# usb_cdcacm.net
KiCad netlist of a schematic drawn in EAGLE
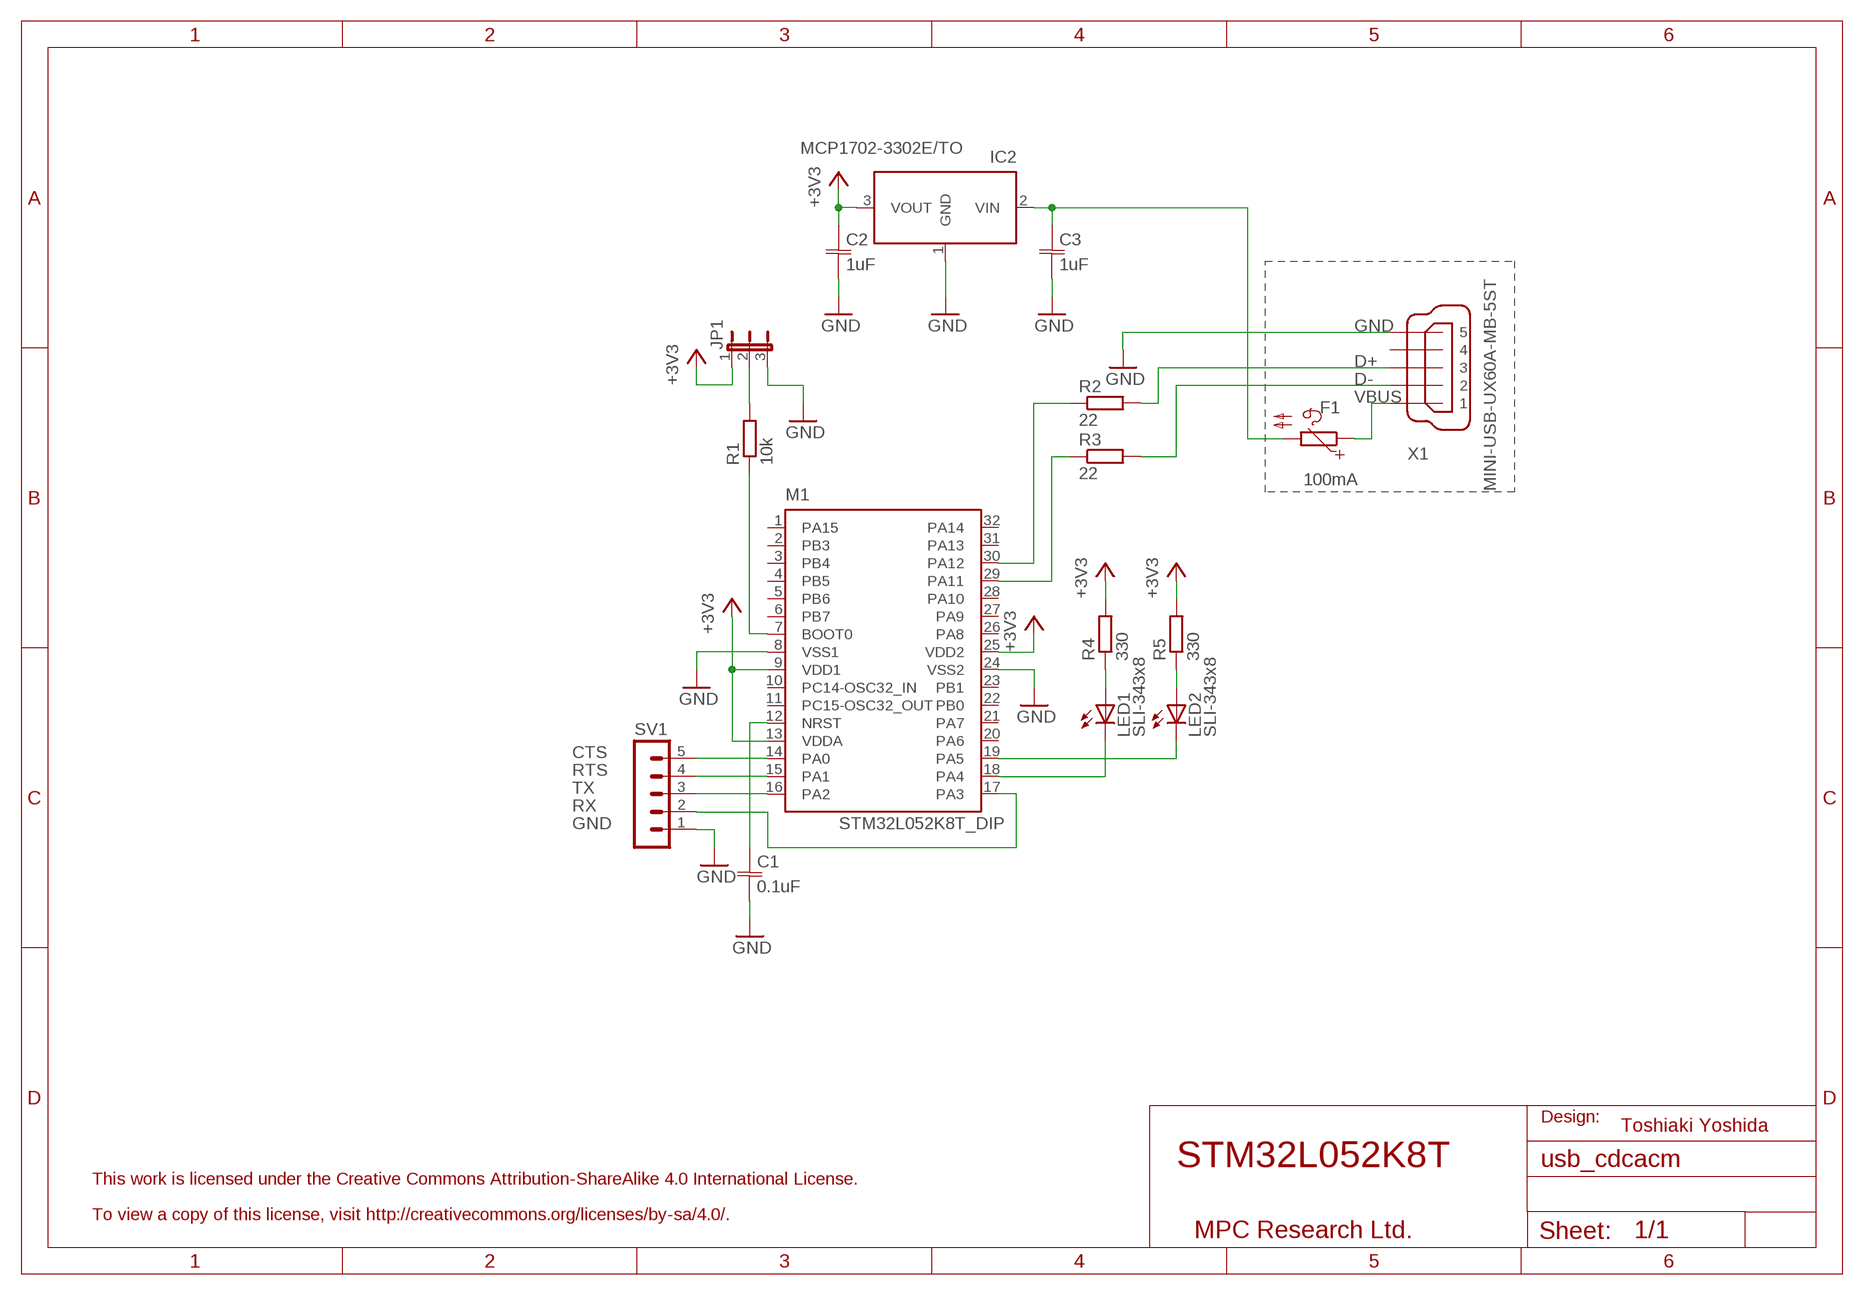
[diagram p0: schematic, sheet 1]

(export (version "E")
  (design (tool "Eeschema 10.0.6"))
  (components
    (comp (ref "C1")
      (value "0.1uF")
      (footprint "eagle-import:C050-024X044")
      (libsource (lib "eagle-import") (part "C-JIS050-024X044"))
    )
    (comp (ref "C2")
      (value "1uF")
      (footprint "eagle-import:C050-024X044")
      (libsource (lib "eagle-import") (part "C-JIS050-024X044"))
    )
    (comp (ref "C3")
      (value "1uF")
      (footprint "eagle-import:C050-024X044")
      (libsource (lib "eagle-import") (part "C-JIS050-024X044"))
    )
    (comp (ref "F1")
      (value "100mA")
      (footprint "eagle-import:1206")
      (libsource (lib "eagle-import") (part "PTC1206"))
    )
    (comp (ref "IC2")
      (value "MCP1702-3302E/TO")
      (footprint "eagle-import:TO92")
      (fields (field (name "VOLTAGE") "3.3V"))
      (libsource (lib "eagle-import") (part "MCP1702TO-3302E/"))
    )
    (comp (ref "JP1")
      (value "JP2E")
      (footprint "eagle-import:JP2")
      (libsource (lib "eagle-import") (part "JP2E"))
    )
    (comp (ref "LED1")
      (value "SLI-343x8")
      (footprint "eagle-import:LED3MM")
      (libsource (lib "eagle-import") (part "LED3MM"))
    )
    (comp (ref "LED2")
      (value "SLI-343x8")
      (footprint "eagle-import:LED3MM")
      (libsource (lib "eagle-import") (part "LED3MM"))
    )
    (comp (ref "M1")
      (value "STM32L052K8T_DIP")
      (footprint "eagle-import:DIP32")
      (libsource (lib "eagle-import") (part "STM32L052K8T_DIP"))
    )
    (comp (ref "R1")
      (value "10k")
      (footprint "eagle-import:0207_2V")
      (libsource (lib "eagle-import") (part "R-EU_0207/2V"))
    )
    (comp (ref "R2")
      (value "22")
      (footprint "eagle-import:0207_10")
      (libsource (lib "eagle-import") (part "R-EU_0207/10"))
    )
    (comp (ref "R3")
      (value "22")
      (footprint "eagle-import:0207_10")
      (libsource (lib "eagle-import") (part "R-EU_0207/10"))
    )
    (comp (ref "R4")
      (value "330")
      (footprint "eagle-import:0207_2V")
      (libsource (lib "eagle-import") (part "R-EU_0207/2V"))
    )
    (comp (ref "R5")
      (value "330")
      (footprint "eagle-import:0207_2V")
      (libsource (lib "eagle-import") (part "R-EU_0207/2V"))
    )
    (comp (ref "SV1")
      (value "MA05-1")
      (footprint "eagle-import:MA05-1")
      (libsource (lib "eagle-import") (part "MA05-1"))
    )
    (comp (ref "X1")
      (value "MINI-USB-UX60A-MB-5ST")
      (footprint "eagle-import:UX60A-MB-5ST")
      (libsource (lib "eagle-import") (part "MINI-USB-UX60A-MB-5ST"))
    )
  )
  (nets
    (net (code "1") (name "+3V3") (class "Default")
      (node (ref "C2") (pin "1") (pinfunction "1_1") (pintype "passive"))
      (node (ref "IC2") (pin "3") (pinfunction "VOUT_3") (pintype "power_in"))
      (node (ref "JP1") (pin "1") (pinfunction "1_1") (pintype "passive"))
      (node (ref "M1") (pin "13") (pinfunction "VDDA_13") (pintype "power_in"))
      (node (ref "M1") (pin "25") (pinfunction "VDD2_25") (pintype "bidirectional"))
      (node (ref "M1") (pin "9") (pinfunction "VDD1_9") (pintype "power_in"))
      (node (ref "R4") (pin "2") (pinfunction "2_2") (pintype "passive"))
      (node (ref "R5") (pin "2") (pinfunction "2_2") (pintype "passive"))
    )
    (net (code "2") (name "GND") (class "Default")
      (node (ref "C1") (pin "2") (pinfunction "2_2") (pintype "passive"))
      (node (ref "C2") (pin "2") (pinfunction "2_2") (pintype "passive"))
      (node (ref "C3") (pin "2") (pinfunction "2_2") (pintype "passive"))
      (node (ref "IC2") (pin "1") (pinfunction "GND_1") (pintype "power_in"))
      (node (ref "JP1") (pin "3") (pinfunction "3_3") (pintype "passive"))
      (node (ref "M1") (pin "24") (pinfunction "VSS2_24") (pintype "power_in"))
      (node (ref "M1") (pin "8") (pinfunction "VSS1_8") (pintype "power_in"))
      (node (ref "SV1") (pin "1") (pinfunction "1_1") (pintype "passive"))
      (node (ref "X1") (pin "5") (pinfunction "5_5") (pintype "input"))
    )
    (net (code "3") (name "Net-(F1-Pad1)") (class "Default")
      (node (ref "F1") (pin "1") (pinfunction "1_1") (pintype "passive"))
      (node (ref "X1") (pin "1") (pinfunction "1_1") (pintype "input"))
    )
    (net (code "4") (name "Net-(IC2-VIN)") (class "Default")
      (node (ref "C3") (pin "1") (pinfunction "1_1") (pintype "passive"))
      (node (ref "F1") (pin "2") (pinfunction "2_2") (pintype "passive"))
      (node (ref "IC2") (pin "2") (pinfunction "VIN_2") (pintype "power_in"))
    )
    (net (code "5") (name "Net-(JP1-Pad2)") (class "Default")
      (node (ref "JP1") (pin "2") (pinfunction "2_2") (pintype "passive"))
      (node (ref "R1") (pin "2") (pinfunction "2_2") (pintype "passive"))
    )
    (net (code "6") (name "Net-(LED1-C)") (class "Default")
      (node (ref "LED1") (pin "K") (pinfunction "C_K") (pintype "passive"))
      (node (ref "M1") (pin "18") (pinfunction "PA4_18") (pintype "bidirectional"))
    )
    (net (code "7") (name "Net-(LED1-PadA)") (class "Default")
      (node (ref "LED1") (pin "A") (pinfunction "A_A") (pintype "passive"))
      (node (ref "R4") (pin "1") (pinfunction "1_1") (pintype "passive"))
    )
    (net (code "8") (name "Net-(LED2-C)") (class "Default")
      (node (ref "LED2") (pin "K") (pinfunction "C_K") (pintype "passive"))
      (node (ref "M1") (pin "19") (pinfunction "PA5_19") (pintype "bidirectional"))
    )
    (net (code "9") (name "Net-(LED2-PadA)") (class "Default")
      (node (ref "LED2") (pin "A") (pinfunction "A_A") (pintype "passive"))
      (node (ref "R5") (pin "1") (pinfunction "1_1") (pintype "passive"))
    )
    (net (code "10") (name "Net-(M1-BOOT0)") (class "Default")
      (node (ref "M1") (pin "7") (pinfunction "BOOT0_7") (pintype "bidirectional"))
      (node (ref "R1") (pin "1") (pinfunction "1_1") (pintype "passive"))
    )
    (net (code "11") (name "Net-(M1-NRST)") (class "Default")
      (node (ref "C1") (pin "1") (pinfunction "1_1") (pintype "passive"))
      (node (ref "M1") (pin "12") (pinfunction "NRST_12") (pintype "bidirectional"))
    )
    (net (code "12") (name "Net-(M1-PA0)") (class "Default")
      (node (ref "M1") (pin "14") (pinfunction "PA0_14") (pintype "bidirectional"))
      (node (ref "SV1") (pin "5") (pinfunction "5_5") (pintype "passive"))
    )
    (net (code "13") (name "Net-(M1-PA1)") (class "Default")
      (node (ref "M1") (pin "15") (pinfunction "PA1_15") (pintype "bidirectional"))
      (node (ref "SV1") (pin "4") (pinfunction "4_4") (pintype "passive"))
    )
    (net (code "14") (name "Net-(M1-PA2)") (class "Default")
      (node (ref "M1") (pin "16") (pinfunction "PA2_16") (pintype "bidirectional"))
      (node (ref "SV1") (pin "3") (pinfunction "3_3") (pintype "passive"))
    )
    (net (code "15") (name "Net-(M1-PA3)") (class "Default")
      (node (ref "M1") (pin "17") (pinfunction "PA3_17") (pintype "bidirectional"))
      (node (ref "SV1") (pin "2") (pinfunction "2_2") (pintype "passive"))
    )
    (net (code "16") (name "Net-(M1-PA11)") (class "Default")
      (node (ref "M1") (pin "29") (pinfunction "PA11_29") (pintype "bidirectional"))
      (node (ref "R3") (pin "1") (pinfunction "1_1") (pintype "passive"))
    )
    (net (code "17") (name "Net-(M1-PA12)") (class "Default")
      (node (ref "M1") (pin "30") (pinfunction "PA12_30") (pintype "bidirectional"))
      (node (ref "R2") (pin "1") (pinfunction "1_1") (pintype "passive"))
    )
    (net (code "18") (name "Net-(R2-Pad2)") (class "Default")
      (node (ref "R2") (pin "2") (pinfunction "2_2") (pintype "passive"))
      (node (ref "X1") (pin "3") (pinfunction "3_3") (pintype "input"))
    )
    (net (code "19") (name "Net-(R3-Pad2)") (class "Default")
      (node (ref "R3") (pin "2") (pinfunction "2_2") (pintype "passive"))
      (node (ref "X1") (pin "2") (pinfunction "2_2") (pintype "input"))
    )
    (net (code "20") (name "unconnected-(M1-PA6-Pad20)") (class "Default")
      (node (ref "M1") (pin "20") (pinfunction "PA6_20") (pintype "bidirectional"))
    )
    (net (code "21") (name "unconnected-(M1-PA7-Pad21)") (class "Default")
      (node (ref "M1") (pin "21") (pinfunction "PA7_21") (pintype "bidirectional"))
    )
    (net (code "22") (name "unconnected-(M1-PA8-Pad26)") (class "Default")
      (node (ref "M1") (pin "26") (pinfunction "PA8_26") (pintype "bidirectional"))
    )
    (net (code "23") (name "unconnected-(M1-PA9-Pad27)") (class "Default")
      (node (ref "M1") (pin "27") (pinfunction "PA9_27") (pintype "bidirectional"))
    )
    (net (code "24") (name "unconnected-(M1-PA10-Pad28)") (class "Default")
      (node (ref "M1") (pin "28") (pinfunction "PA10_28") (pintype "bidirectional"))
    )
    (net (code "25") (name "unconnected-(M1-PA13-Pad31)") (class "Default")
      (node (ref "M1") (pin "31") (pinfunction "PA13_31") (pintype "bidirectional"))
    )
    (net (code "26") (name "unconnected-(M1-PA14-Pad32)") (class "Default")
      (node (ref "M1") (pin "32") (pinfunction "PA14_32") (pintype "bidirectional"))
    )
    (net (code "27") (name "unconnected-(M1-PA15-Pad1)") (class "Default")
      (node (ref "M1") (pin "1") (pinfunction "PA15_1") (pintype "bidirectional"))
    )
    (net (code "28") (name "unconnected-(M1-PB0-Pad22)") (class "Default")
      (node (ref "M1") (pin "22") (pinfunction "PB0_22") (pintype "bidirectional"))
    )
    (net (code "29") (name "unconnected-(M1-PB1-Pad23)") (class "Default")
      (node (ref "M1") (pin "23") (pinfunction "PB1_23") (pintype "bidirectional"))
    )
    (net (code "30") (name "unconnected-(M1-PB3-Pad2)") (class "Default")
      (node (ref "M1") (pin "2") (pinfunction "PB3_2") (pintype "bidirectional"))
    )
    (net (code "31") (name "unconnected-(M1-PB4-Pad3)") (class "Default")
      (node (ref "M1") (pin "3") (pinfunction "PB4_3") (pintype "bidirectional"))
    )
    (net (code "32") (name "unconnected-(M1-PB5-Pad4)") (class "Default")
      (node (ref "M1") (pin "4") (pinfunction "PB5_4") (pintype "bidirectional"))
    )
    (net (code "33") (name "unconnected-(M1-PB6-Pad5)") (class "Default")
      (node (ref "M1") (pin "5") (pinfunction "PB6_5") (pintype "bidirectional"))
    )
    (net (code "34") (name "unconnected-(M1-PB7-Pad6)") (class "Default")
      (node (ref "M1") (pin "6") (pinfunction "PB7_6") (pintype "bidirectional"))
    )
    (net (code "35") (name "unconnected-(M1-PC14-OSC32_IN-Pad10)") (class "Default")
      (node (ref "M1") (pin "10") (pinfunction "PC14-OSC32_IN_10") (pintype "bidirectional"))
    )
    (net (code "36") (name "unconnected-(M1-PC15-OSC32_OUT-Pad11)") (class "Default")
      (node (ref "M1") (pin "11") (pinfunction "PC15-OSC32_OUT_11") (pintype "bidirectional"))
    )
    (net (code "37") (name "unconnected-(X1-Pad4)") (class "Default")
      (node (ref "X1") (pin "4") (pinfunction "4_4") (pintype "input"))
    )
  )
)
